# SoC_PS_505_GTR.net
KiCad netlist of a schematic drawn in Altium Designer
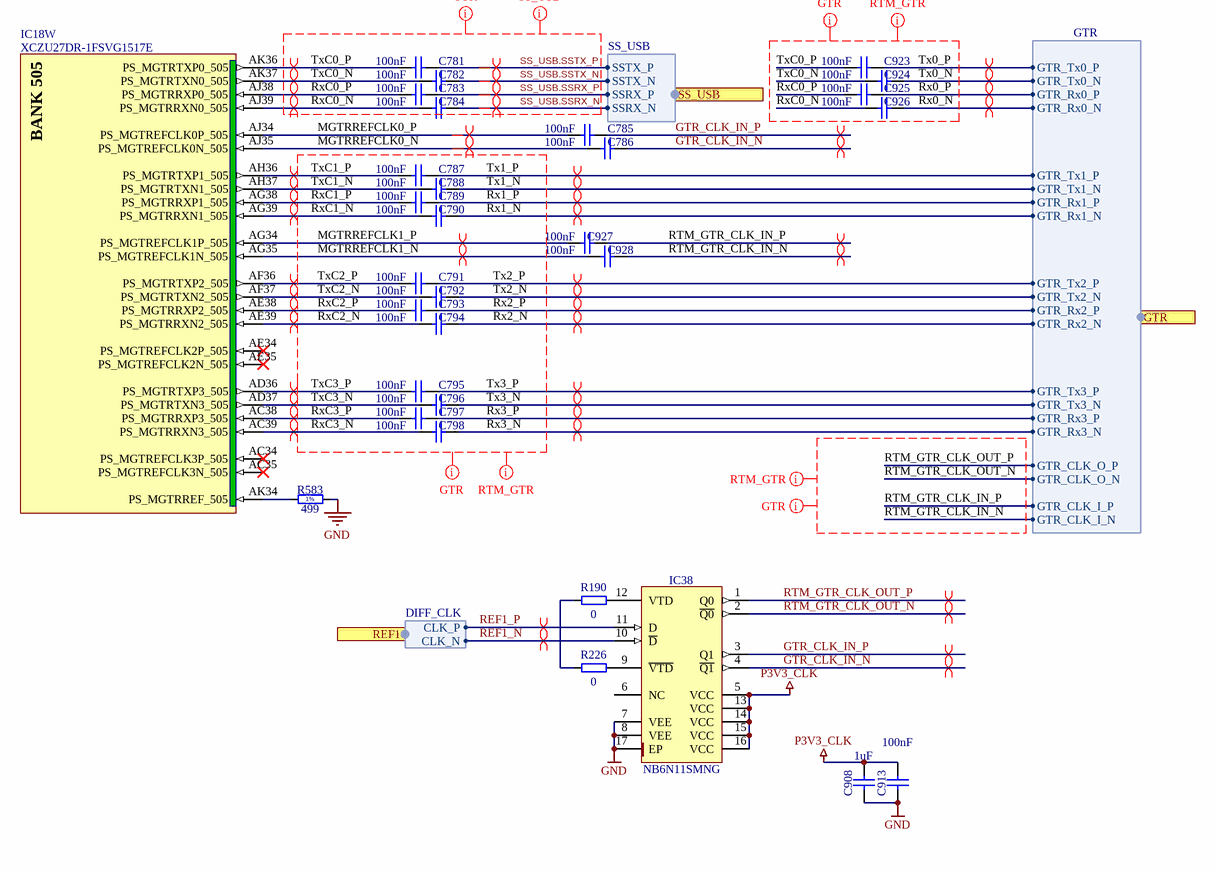
[diagram p0: SoC_PS_505_GTR.SchDoc]

(export (version "E")
  (design (tool "Eeschema 10.0.6"))
  (components
    (comp (ref "C781")
      (value "100nF")
      (footprint "CAPC0603X33N")
      (description "Non-polarised capacitor")
      (fields
        (field (name "PART NUMBER") "CC0201_100NF_6.3V_10%_X5R")
        (field (name "VOLTAGE") "6.3V")
        (field (name "AUTHOR") "CERN DEM JLC")
      )
      (libsource (lib "Capacitors") (part "Capacitor - non polarized"))
    )
    (comp (ref "C782")
      (value "100nF")
      (footprint "CAPC0603X33N")
      (description "Non-polarised capacitor")
      (fields
        (field (name "PART NUMBER") "CC0201_100NF_6.3V_10%_X5R")
        (field (name "VOLTAGE") "6.3V")
        (field (name "AUTHOR") "CERN DEM JLC")
      )
      (libsource (lib "Capacitors") (part "Capacitor - non polarized"))
    )
    (comp (ref "C783")
      (value "100nF")
      (footprint "CAPC0603X33N")
      (description "Non-polarised capacitor")
      (fields
        (field (name "PART NUMBER") "CC0201_100NF_6.3V_10%_X5R")
        (field (name "VOLTAGE") "6.3V")
        (field (name "AUTHOR") "CERN DEM JLC")
      )
      (libsource (lib "Capacitors") (part "Capacitor - non polarized"))
    )
    (comp (ref "C784")
      (value "100nF")
      (footprint "CAPC0603X33N")
      (description "Non-polarised capacitor")
      (fields
        (field (name "PART NUMBER") "CC0201_100NF_6.3V_10%_X5R")
        (field (name "VOLTAGE") "6.3V")
        (field (name "AUTHOR") "CERN DEM JLC")
      )
      (libsource (lib "Capacitors") (part "Capacitor - non polarized"))
    )
    (comp (ref "C785")
      (value "100nF")
      (footprint "CAPC0603X33N")
      (description "Non-polarised capacitor")
      (fields
        (field (name "PART NUMBER") "CC0201_100NF_6.3V_10%_X5R")
        (field (name "VOLTAGE") "6.3V")
        (field (name "AUTHOR") "CERN DEM JLC")
      )
      (libsource (lib "Capacitors") (part "Capacitor - non polarized"))
    )
    (comp (ref "C786")
      (value "100nF")
      (footprint "CAPC0603X33N")
      (description "Non-polarised capacitor")
      (fields
        (field (name "PART NUMBER") "CC0201_100NF_6.3V_10%_X5R")
        (field (name "VOLTAGE") "6.3V")
        (field (name "AUTHOR") "CERN DEM JLC")
      )
      (libsource (lib "Capacitors") (part "Capacitor - non polarized"))
    )
    (comp (ref "C787")
      (value "100nF")
      (footprint "CAPC0603X33N")
      (description "Non-polarised capacitor")
      (fields
        (field (name "PART NUMBER") "CC0201_100NF_6.3V_10%_X5R")
        (field (name "VOLTAGE") "6.3V")
        (field (name "AUTHOR") "CERN DEM JLC")
      )
      (libsource (lib "Capacitors") (part "Capacitor - non polarized"))
    )
    (comp (ref "C788")
      (value "100nF")
      (footprint "CAPC0603X33N")
      (description "Non-polarised capacitor")
      (fields
        (field (name "PART NUMBER") "CC0201_100NF_6.3V_10%_X5R")
        (field (name "VOLTAGE") "6.3V")
        (field (name "AUTHOR") "CERN DEM JLC")
      )
      (libsource (lib "Capacitors") (part "Capacitor - non polarized"))
    )
    (comp (ref "C789")
      (value "100nF")
      (footprint "CAPC0603X33N")
      (description "Non-polarised capacitor")
      (fields
        (field (name "PART NUMBER") "CC0201_100NF_6.3V_10%_X5R")
        (field (name "VOLTAGE") "6.3V")
        (field (name "AUTHOR") "CERN DEM JLC")
      )
      (libsource (lib "Capacitors") (part "Capacitor - non polarized"))
    )
    (comp (ref "C790")
      (value "100nF")
      (footprint "CAPC0603X33N")
      (description "Non-polarised capacitor")
      (fields
        (field (name "PART NUMBER") "CC0201_100NF_6.3V_10%_X5R")
        (field (name "VOLTAGE") "6.3V")
        (field (name "AUTHOR") "CERN DEM JLC")
      )
      (libsource (lib "Capacitors") (part "Capacitor - non polarized"))
    )
    (comp (ref "C791")
      (value "100nF")
      (footprint "CAPC0603X33N")
      (description "Non-polarised capacitor")
      (fields
        (field (name "PART NUMBER") "CC0201_100NF_6.3V_10%_X5R")
        (field (name "VOLTAGE") "6.3V")
        (field (name "AUTHOR") "CERN DEM JLC")
      )
      (libsource (lib "Capacitors") (part "Capacitor - non polarized"))
    )
    (comp (ref "C792")
      (value "100nF")
      (footprint "CAPC0603X33N")
      (description "Non-polarised capacitor")
      (fields
        (field (name "PART NUMBER") "CC0201_100NF_6.3V_10%_X5R")
        (field (name "VOLTAGE") "6.3V")
        (field (name "AUTHOR") "CERN DEM JLC")
      )
      (libsource (lib "Capacitors") (part "Capacitor - non polarized"))
    )
    (comp (ref "C793")
      (value "100nF")
      (footprint "CAPC0603X33N")
      (description "Non-polarised capacitor")
      (fields
        (field (name "PART NUMBER") "CC0201_100NF_6.3V_10%_X5R")
        (field (name "VOLTAGE") "6.3V")
        (field (name "AUTHOR") "CERN DEM JLC")
      )
      (libsource (lib "Capacitors") (part "Capacitor - non polarized"))
    )
    (comp (ref "C794")
      (value "100nF")
      (footprint "CAPC0603X33N")
      (description "Non-polarised capacitor")
      (fields
        (field (name "PART NUMBER") "CC0201_100NF_6.3V_10%_X5R")
        (field (name "VOLTAGE") "6.3V")
        (field (name "AUTHOR") "CERN DEM JLC")
      )
      (libsource (lib "Capacitors") (part "Capacitor - non polarized"))
    )
    (comp (ref "C795")
      (value "100nF")
      (footprint "CAPC0603X33N")
      (description "Non-polarised capacitor")
      (fields
        (field (name "PART NUMBER") "CC0201_100NF_6.3V_10%_X5R")
        (field (name "VOLTAGE") "6.3V")
        (field (name "AUTHOR") "CERN DEM JLC")
      )
      (libsource (lib "Capacitors") (part "Capacitor - non polarized"))
    )
    (comp (ref "C796")
      (value "100nF")
      (footprint "CAPC0603X33N")
      (description "Non-polarised capacitor")
      (fields
        (field (name "PART NUMBER") "CC0201_100NF_6.3V_10%_X5R")
        (field (name "VOLTAGE") "6.3V")
        (field (name "AUTHOR") "CERN DEM JLC")
      )
      (libsource (lib "Capacitors") (part "Capacitor - non polarized"))
    )
    (comp (ref "C797")
      (value "100nF")
      (footprint "CAPC0603X33N")
      (description "Non-polarised capacitor")
      (fields
        (field (name "PART NUMBER") "CC0201_100NF_6.3V_10%_X5R")
        (field (name "VOLTAGE") "6.3V")
        (field (name "AUTHOR") "CERN DEM JLC")
      )
      (libsource (lib "Capacitors") (part "Capacitor - non polarized"))
    )
    (comp (ref "C798")
      (value "100nF")
      (footprint "CAPC0603X33N")
      (description "Non-polarised capacitor")
      (fields
        (field (name "PART NUMBER") "CC0201_100NF_6.3V_10%_X5R")
        (field (name "VOLTAGE") "6.3V")
        (field (name "AUTHOR") "CERN DEM JLC")
      )
      (libsource (lib "Capacitors") (part "Capacitor - non polarized"))
    )
    (comp (ref "C908")
      (value "1uF")
      (footprint "CAPC1005X55N")
      (description "Non-polarised capacitor")
      (fields
        (field (name "MANUFACTURER PART NUMBER") "CC0402_1UF_16V_10%_X5R")
        (field (name "MANUFACTURER") "GENERIC")
        (field (name "AUTHOR") "CERN DEM JLC")
      )
      (libsource (lib "Capacitors") (part "Capacitor - non polarized"))
    )
    (comp (ref "C913")
      (value "100nF")
      (footprint "CAPC0603X33N")
      (description "Non-polarised capacitor")
      (fields
        (field (name "MANUFACTURER PART NUMBER") "CC0201_100NF_6.3V_10%_X5R")
        (field (name "MANUFACTURER") "GENERIC")
        (field (name "AUTHOR") "CERN DEM JLC")
      )
      (libsource (lib "Capacitors") (part "Capacitor - non polarized"))
    )
    (comp (ref "C923")
      (value "100nF")
      (footprint "CAPC0603X33N")
      (description "Non-polarised capacitor")
      (fields
        (field (name "PART NUMBER") "CC0201_100NF_6.3V_10%_X5R")
        (field (name "VOLTAGE") "6.3V")
        (field (name "AUTHOR") "CERN DEM JLC")
      )
      (libsource (lib "Capacitors") (part "Capacitor - non polarized"))
    )
    (comp (ref "C924")
      (value "100nF")
      (footprint "CAPC0603X33N")
      (description "Non-polarised capacitor")
      (fields
        (field (name "PART NUMBER") "CC0201_100NF_6.3V_10%_X5R")
        (field (name "VOLTAGE") "6.3V")
        (field (name "AUTHOR") "CERN DEM JLC")
      )
      (libsource (lib "Capacitors") (part "Capacitor - non polarized"))
    )
    (comp (ref "C925")
      (value "100nF")
      (footprint "CAPC0603X33N")
      (description "Non-polarised capacitor")
      (fields
        (field (name "PART NUMBER") "CC0201_100NF_6.3V_10%_X5R")
        (field (name "VOLTAGE") "6.3V")
        (field (name "AUTHOR") "CERN DEM JLC")
      )
      (libsource (lib "Capacitors") (part "Capacitor - non polarized"))
    )
    (comp (ref "C926")
      (value "100nF")
      (footprint "CAPC0603X33N")
      (description "Non-polarised capacitor")
      (fields
        (field (name "PART NUMBER") "CC0201_100NF_6.3V_10%_X5R")
        (field (name "VOLTAGE") "6.3V")
        (field (name "AUTHOR") "CERN DEM JLC")
      )
      (libsource (lib "Capacitors") (part "Capacitor - non polarized"))
    )
    (comp (ref "C927")
      (value "100nF")
      (footprint "CAPC0603X33N")
      (description "Non-polarised capacitor")
      (fields
        (field (name "PART NUMBER") "CC0201_100NF_6.3V_10%_X5R")
        (field (name "VOLTAGE") "6.3V")
        (field (name "AUTHOR") "CERN DEM JLC")
      )
      (libsource (lib "Capacitors") (part "Capacitor - non polarized"))
    )
    (comp (ref "C928")
      (value "100nF")
      (footprint "CAPC0603X33N")
      (description "Non-polarised capacitor")
      (fields
        (field (name "PART NUMBER") "CC0201_100NF_6.3V_10%_X5R")
        (field (name "VOLTAGE") "6.3V")
        (field (name "AUTHOR") "CERN DEM JLC")
      )
      (libsource (lib "Capacitors") (part "Capacitor - non polarized"))
    )
    (comp (ref "IC18")
      (value "XCZU27DR-1FSVG1517E")
      (footprint "XILINX_FSVG1517 (XCZU27DR)")
      (fields (field (name "MANUFACTURER") "XILINX") (field (name "AUTHOR") "CERN DEM MR"))
      (libsource (lib "ICs And Semiconductors") (part "XCZU27DR-1FSVG1517E"))
    )
    (comp (ref "IC38")
      (value "NB6N11SMNG")
      (footprint "QFN50P300X300X100-17N-S185")
      (description "3.3V 1:2 AnyLevel Input to LVDS Fanout Buffer / Translator")
      (fields (field (name "MANUFACTURER") "ON SEMICONDUCTOR") (field (name "AUTHOR") "CERN DEM JLC"))
      (libsource (lib "ICs And Semiconductors") (part "NB6N11SMN"))
    )
    (comp (ref "R190")
      (value "0")
      (footprint "RESC1005X40N")
      (description "Resistor")
      (fields
        (field (name "PART NUMBER") "R0402_0R_JUMPER")
        (field (name "MANUFACTURER") "GENERIC")
        (field (name "AUTHOR") "CERN DEM JLC")
      )
      (libsource (lib "Resistors") (part "Resistor"))
    )
    (comp (ref "R226")
      (value "0")
      (footprint "RESC1005X40N")
      (description "Resistor")
      (fields
        (field (name "PART NUMBER") "R0402_0R_JUMPER")
        (field (name "MANUFACTURER") "GENERIC")
        (field (name "AUTHOR") "CERN DEM JLC")
      )
      (libsource (lib "Resistors") (part "Resistor"))
    )
    (comp (ref "R583")
      (value "499")
      (footprint "RESC1005X40N")
      (description "Resistor - 1%")
      (fields
        (field (name "PART NUMBER") "R0402_499R_1%_0.1W_100PPM")
        (field (name "POWER") "0.1W")
        (field (name "AUTHOR") "CERN DEM MR")
      )
      (libsource (lib "Resistors") (part "Resistor - 1%"))
    )
  )
  (nets
    (net (code "4") (name "/GTR_CLK_IN_N") (class "Default")
      (node (ref "C786") (pin "2") (pinfunction "2_2") (pintype "passive"))
      (node (ref "IC38") (pin "4") (pinfunction "~{Q1}_4") (pintype "output"))
    )
    (net (code "5") (name "/GTR_CLK_IN_P") (class "Default")
      (node (ref "C785") (pin "2") (pinfunction "2_2") (pintype "passive"))
      (node (ref "IC38") (pin "3") (pinfunction "Q1_3") (pintype "output"))
    )
    (net (code "6") (name "/MGTRREFCLK0_N") (class "Default")
      (node (ref "C786") (pin "1") (pinfunction "1_1") (pintype "passive"))
      (node (ref "IC18") (pin "AJ35") (pinfunction "PS_MGTREFCLK0N_505_AJ35") (pintype "input"))
    )
    (net (code "7") (name "/MGTRREFCLK0_P") (class "Default")
      (node (ref "C785") (pin "1") (pinfunction "1_1") (pintype "passive"))
      (node (ref "IC18") (pin "AJ34") (pinfunction "PS_MGTREFCLK0P_505_AJ34") (pintype "input"))
    )
    (net (code "8") (name "/MGTRREFCLK1_N") (class "Default")
      (node (ref "C928") (pin "1") (pinfunction "1_1") (pintype "passive"))
      (node (ref "IC18") (pin "AG35") (pinfunction "PS_MGTREFCLK1N_505_AG35") (pintype "input"))
    )
    (net (code "9") (name "/MGTRREFCLK1_P") (class "Default")
      (node (ref "C927") (pin "1") (pinfunction "1_1") (pintype "passive"))
      (node (ref "IC18") (pin "AG34") (pinfunction "PS_MGTREFCLK1P_505_AG34") (pintype "input"))
    )
    (net (code "10") (name "/REF1_N") (class "Default")
      (node (ref "IC38") (pin "10") (pinfunction "~{D}_10") (pintype "input"))
    )
    (net (code "11") (name "/REF1_P") (class "Default")
      (node (ref "IC38") (pin "11") (pinfunction "D_11") (pintype "input"))
    )
    (net (code "12") (name "/RTM_GTR_CLK_IN_N") (class "Default")
      (node (ref "C928") (pin "2") (pinfunction "2_2") (pintype "passive"))
    )
    (net (code "13") (name "/RTM_GTR_CLK_IN_P") (class "Default")
      (node (ref "C927") (pin "2") (pinfunction "2_2") (pintype "passive"))
    )
    (net (code "14") (name "/RTM_GTR_CLK_OUT_N") (class "Default")
      (node (ref "IC38") (pin "2") (pinfunction "~{Q0}_2") (pintype "output"))
    )
    (net (code "15") (name "/RTM_GTR_CLK_OUT_P") (class "Default")
      (node (ref "IC38") (pin "1") (pinfunction "Q0_1") (pintype "output"))
    )
    (net (code "16") (name "/Rx0_N") (class "Default")
      (node (ref "C926") (pin "2") (pinfunction "2_2") (pintype "passive"))
    )
    (net (code "17") (name "/Rx0_P") (class "Default")
      (node (ref "C925") (pin "2") (pinfunction "2_2") (pintype "passive"))
    )
    (net (code "18") (name "/Rx1_N") (class "Default")
      (node (ref "C790") (pin "2") (pinfunction "2_2") (pintype "passive"))
    )
    (net (code "19") (name "/Rx1_P") (class "Default")
      (node (ref "C789") (pin "2") (pinfunction "2_2") (pintype "passive"))
    )
    (net (code "20") (name "/Rx2_N") (class "Default")
      (node (ref "C794") (pin "2") (pinfunction "2_2") (pintype "passive"))
    )
    (net (code "21") (name "/Rx2_P") (class "Default")
      (node (ref "C793") (pin "2") (pinfunction "2_2") (pintype "passive"))
    )
    (net (code "22") (name "/Rx3_N") (class "Default")
      (node (ref "C798") (pin "2") (pinfunction "2_2") (pintype "passive"))
    )
    (net (code "23") (name "/Rx3_P") (class "Default")
      (node (ref "C797") (pin "2") (pinfunction "2_2") (pintype "passive"))
    )
    (net (code "24") (name "/RxC0_N") (class "Default")
      (node (ref "C784") (pin "1") (pinfunction "1_1") (pintype "passive"))
      (node (ref "C926") (pin "1") (pinfunction "1_1") (pintype "passive"))
      (node (ref "IC18") (pin "AJ39") (pinfunction "PS_MGTRRXN0_505_AJ39") (pintype "input"))
    )
    (net (code "25") (name "/RxC0_P") (class "Default")
      (node (ref "C783") (pin "1") (pinfunction "1_1") (pintype "passive"))
      (node (ref "C925") (pin "1") (pinfunction "1_1") (pintype "passive"))
      (node (ref "IC18") (pin "AJ38") (pinfunction "PS_MGTRRXP0_505_AJ38") (pintype "input"))
    )
    (net (code "26") (name "/RxC1_N") (class "Default")
      (node (ref "C790") (pin "1") (pinfunction "1_1") (pintype "passive"))
      (node (ref "IC18") (pin "AG39") (pinfunction "PS_MGTRRXN1_505_AG39") (pintype "input"))
    )
    (net (code "27") (name "/RxC1_P") (class "Default")
      (node (ref "C789") (pin "1") (pinfunction "1_1") (pintype "passive"))
      (node (ref "IC18") (pin "AG38") (pinfunction "PS_MGTRRXP1_505_AG38") (pintype "input"))
    )
    (net (code "28") (name "/RxC2_N") (class "Default")
      (node (ref "C794") (pin "1") (pinfunction "1_1") (pintype "passive"))
      (node (ref "IC18") (pin "AE39") (pinfunction "PS_MGTRRXN2_505_AE39") (pintype "input"))
    )
    (net (code "29") (name "/RxC2_P") (class "Default")
      (node (ref "C793") (pin "1") (pinfunction "1_1") (pintype "passive"))
      (node (ref "IC18") (pin "AE38") (pinfunction "PS_MGTRRXP2_505_AE38") (pintype "input"))
    )
    (net (code "30") (name "/RxC3_N") (class "Default")
      (node (ref "C798") (pin "1") (pinfunction "1_1") (pintype "passive"))
      (node (ref "IC18") (pin "AC39") (pinfunction "PS_MGTRRXN3_505_AC39") (pintype "input"))
    )
    (net (code "31") (name "/RxC3_P") (class "Default")
      (node (ref "C797") (pin "1") (pinfunction "1_1") (pintype "passive"))
      (node (ref "IC18") (pin "AC38") (pinfunction "PS_MGTRRXP3_505_AC38") (pintype "input"))
    )
    (net (code "32") (name "/SS_USB.SSRX_N") (class "Default")
      (node (ref "C784") (pin "2") (pinfunction "2_2") (pintype "passive"))
    )
    (net (code "33") (name "/SS_USB.SSRX_P") (class "Default")
      (node (ref "C783") (pin "2") (pinfunction "2_2") (pintype "passive"))
    )
    (net (code "34") (name "/SS_USB.SSTX_N") (class "Default")
      (node (ref "C782") (pin "2") (pinfunction "2_2") (pintype "passive"))
    )
    (net (code "35") (name "/SS_USB.SSTX_P") (class "Default")
      (node (ref "C781") (pin "2") (pinfunction "2_2") (pintype "passive"))
    )
    (net (code "36") (name "/Tx0_N") (class "Default")
      (node (ref "C924") (pin "2") (pinfunction "2_2") (pintype "passive"))
    )
    (net (code "37") (name "/Tx0_P") (class "Default")
      (node (ref "C923") (pin "2") (pinfunction "2_2") (pintype "passive"))
    )
    (net (code "38") (name "/Tx1_N") (class "Default")
      (node (ref "C788") (pin "2") (pinfunction "2_2") (pintype "passive"))
    )
    (net (code "39") (name "/Tx1_P") (class "Default")
      (node (ref "C787") (pin "2") (pinfunction "2_2") (pintype "passive"))
    )
    (net (code "40") (name "/Tx2_N") (class "Default")
      (node (ref "C792") (pin "2") (pinfunction "2_2") (pintype "passive"))
    )
    (net (code "41") (name "/Tx2_P") (class "Default")
      (node (ref "C791") (pin "2") (pinfunction "2_2") (pintype "passive"))
    )
    (net (code "42") (name "/Tx3_N") (class "Default")
      (node (ref "C796") (pin "2") (pinfunction "2_2") (pintype "passive"))
    )
    (net (code "43") (name "/Tx3_P") (class "Default")
      (node (ref "C795") (pin "2") (pinfunction "2_2") (pintype "passive"))
    )
    (net (code "44") (name "/TxC0_N") (class "Default")
      (node (ref "C782") (pin "1") (pinfunction "1_1") (pintype "passive"))
      (node (ref "C924") (pin "1") (pinfunction "1_1") (pintype "passive"))
      (node (ref "IC18") (pin "AK37") (pinfunction "PS_MGTRTXN0_505_AK37") (pintype "output"))
    )
    (net (code "45") (name "/TxC0_P") (class "Default")
      (node (ref "C781") (pin "1") (pinfunction "1_1") (pintype "passive"))
      (node (ref "C923") (pin "1") (pinfunction "1_1") (pintype "passive"))
      (node (ref "IC18") (pin "AK36") (pinfunction "PS_MGTRTXP0_505_AK36") (pintype "output"))
    )
    (net (code "46") (name "/TxC1_N") (class "Default")
      (node (ref "C788") (pin "1") (pinfunction "1_1") (pintype "passive"))
      (node (ref "IC18") (pin "AH37") (pinfunction "PS_MGTRTXN1_505_AH37") (pintype "output"))
    )
    (net (code "47") (name "/TxC1_P") (class "Default")
      (node (ref "C787") (pin "1") (pinfunction "1_1") (pintype "passive"))
      (node (ref "IC18") (pin "AH36") (pinfunction "PS_MGTRTXP1_505_AH36") (pintype "output"))
    )
    (net (code "48") (name "/TxC2_N") (class "Default")
      (node (ref "C792") (pin "1") (pinfunction "1_1") (pintype "passive"))
      (node (ref "IC18") (pin "AF37") (pinfunction "PS_MGTRTXN2_505_AF37") (pintype "output"))
    )
    (net (code "49") (name "/TxC2_P") (class "Default")
      (node (ref "C791") (pin "1") (pinfunction "1_1") (pintype "passive"))
      (node (ref "IC18") (pin "AF36") (pinfunction "PS_MGTRTXP2_505_AF36") (pintype "output"))
    )
    (net (code "50") (name "/TxC3_N") (class "Default")
      (node (ref "C796") (pin "1") (pinfunction "1_1") (pintype "passive"))
      (node (ref "IC18") (pin "AD37") (pinfunction "PS_MGTRTXN3_505_AD37") (pintype "output"))
    )
    (net (code "51") (name "/TxC3_P") (class "Default")
      (node (ref "C795") (pin "1") (pinfunction "1_1") (pintype "passive"))
      (node (ref "IC18") (pin "AD36") (pinfunction "PS_MGTRTXP3_505_AD36") (pintype "output"))
    )
    (net (code "55") (name "GND") (class "Default")
      (node (ref "C908") (pin "2") (pinfunction "2_2") (pintype "passive"))
      (node (ref "C913") (pin "1") (pinfunction "1_1") (pintype "passive"))
      (node (ref "IC38") (pin "17") (pinfunction "EP_17") (pintype "power_in"))
      (node (ref "IC38") (pin "7") (pinfunction "VEE_7") (pintype "power_in"))
      (node (ref "IC38") (pin "8") (pinfunction "VEE_8") (pintype "power_in"))
      (node (ref "R583") (pin "2") (pinfunction "2_2") (pintype "passive"))
    )
    (net (code "56") (name "Net-(IC18W-PS_MGTRREF_505)") (class "Default")
      (node (ref "IC18") (pin "AK34") (pinfunction "PS_MGTRREF_505_AK34") (pintype "input"))
      (node (ref "R583") (pin "1") (pinfunction "1_1") (pintype "passive"))
    )
    (net (code "57") (name "Net-(IC38-VTD)") (class "Default")
      (node (ref "IC38") (pin "12") (pinfunction "VTD_12") (pintype "passive"))
      (node (ref "R190") (pin "2") (pinfunction "2_2") (pintype "passive"))
    )
    (net (code "58") (name "Net-(IC38-~{VTD})") (class "Default")
      (node (ref "IC38") (pin "9") (pinfunction "~{VTD}_9") (pintype "passive"))
      (node (ref "R226") (pin "2") (pinfunction "2_2") (pintype "passive"))
    )
    (net (code "59") (name "Net-(R190-Pad1)") (class "Default")
      (node (ref "R190") (pin "1") (pinfunction "1_1") (pintype "passive"))
      (node (ref "R226") (pin "1") (pinfunction "1_1") (pintype "passive"))
    )
    (net (code "60") (name "P3V3_CLK") (class "Default")
      (node (ref "C908") (pin "1") (pinfunction "1_1") (pintype "passive"))
      (node (ref "C913") (pin "2") (pinfunction "2_2") (pintype "passive"))
      (node (ref "IC38") (pin "13") (pinfunction "VCC_13") (pintype "power_in"))
      (node (ref "IC38") (pin "14") (pinfunction "VCC_14") (pintype "power_in"))
      (node (ref "IC38") (pin "15") (pinfunction "VCC_15") (pintype "power_in"))
      (node (ref "IC38") (pin "16") (pinfunction "VCC_16") (pintype "power_in"))
      (node (ref "IC38") (pin "5") (pinfunction "VCC_5") (pintype "power_in"))
    )
    (net (code "61") (name "unconnected-(IC18W-PS_MGTREFCLK2N_505-PadAE35)") (class "Default")
      (node (ref "IC18") (pin "AE35") (pinfunction "PS_MGTREFCLK2N_505_AE35") (pintype "input+no_connect"))
    )
    (net (code "62") (name "unconnected-(IC18W-PS_MGTREFCLK2P_505-PadAE34)") (class "Default")
      (node (ref "IC18") (pin "AE34") (pinfunction "PS_MGTREFCLK2P_505_AE34") (pintype "input+no_connect"))
    )
    (net (code "63") (name "unconnected-(IC18W-PS_MGTREFCLK3N_505-PadAC35)") (class "Default")
      (node (ref "IC18") (pin "AC35") (pinfunction "PS_MGTREFCLK3N_505_AC35") (pintype "input+no_connect"))
    )
    (net (code "64") (name "unconnected-(IC18W-PS_MGTREFCLK3P_505-PadAC34)") (class "Default")
      (node (ref "IC18") (pin "AC34") (pinfunction "PS_MGTREFCLK3P_505_AC34") (pintype "input+no_connect"))
    )
    (net (code "65") (name "unconnected-(IC38-NC-Pad6)") (class "Default")
      (node (ref "IC38") (pin "6") (pinfunction "NC_6") (pintype "passive"))
    )
  )
)
